# 06_LED_Config.net
KiCad netlist of a schematic drawn in Altium Designer
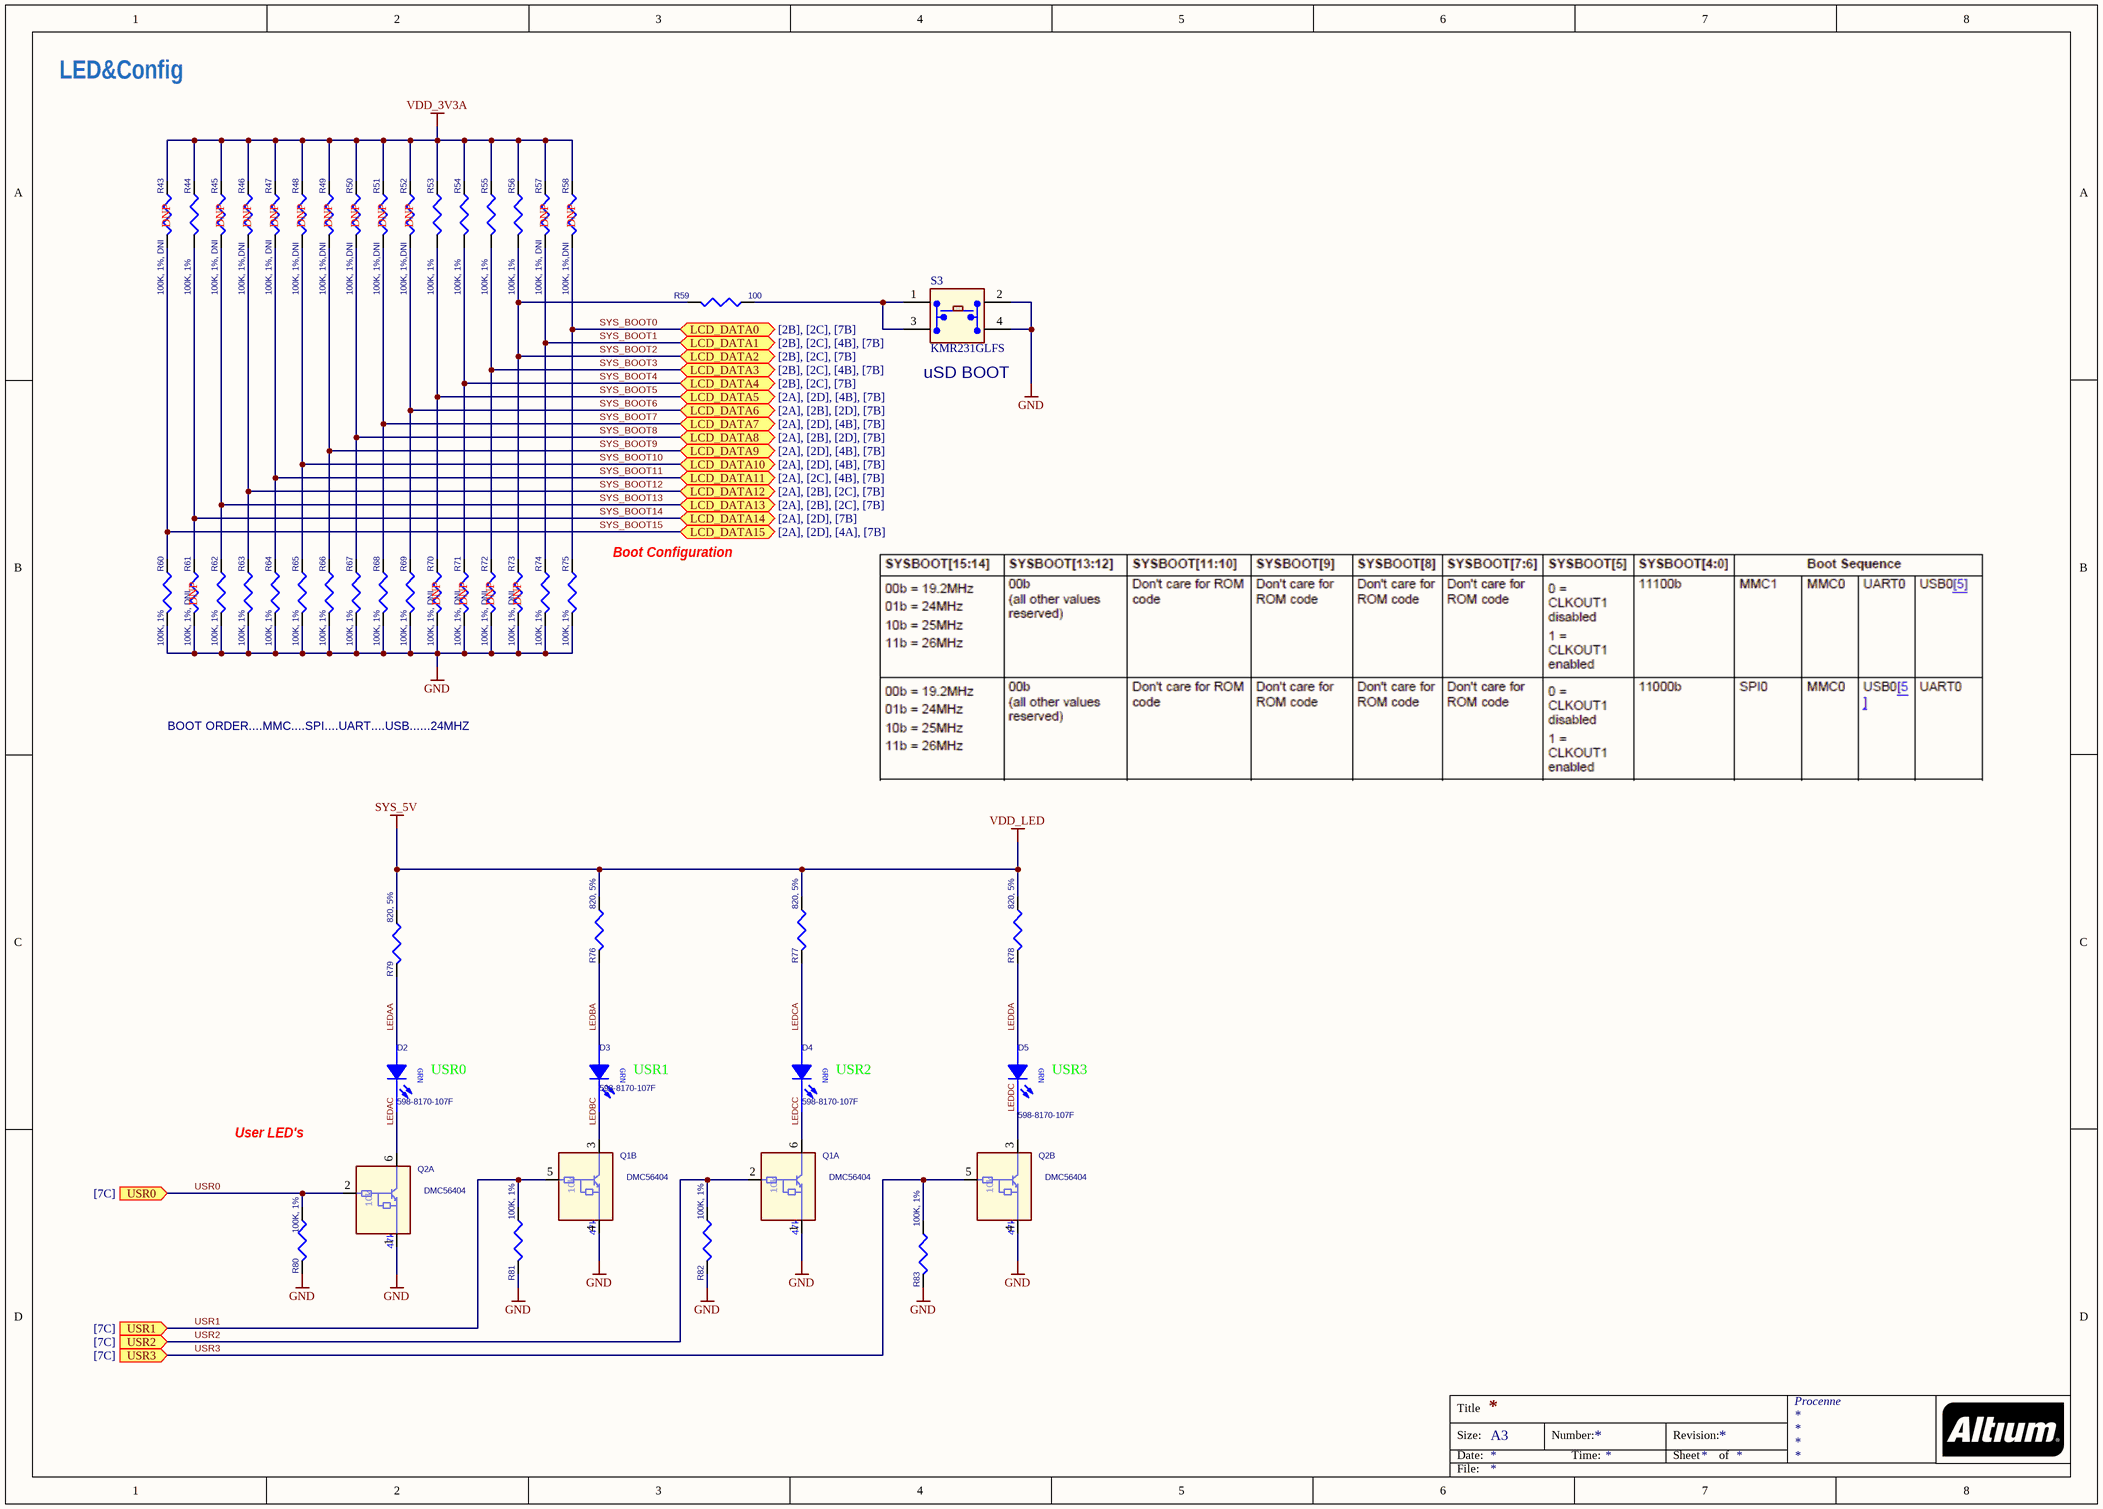
[diagram p0: 06_LED&Config.SchDoc]

(export (version "E")
  (design (tool "Eeschema 10.0.6"))
  (components
    (comp (ref "D2")
      (value "598-8170-107F")
      (footprint "LED_0603")
      (description "LED GREEN CLEAR 0805 SMD")
      (fields
        (field (name "MANUFACTURER") "Lite-On Inc")
        (field (name "MANUFACTURER PART NUMBER") "LTST-C170KGKT")
      )
      (libsource (lib "BEAGLEBONEBLACK_REV A5B") (part "LED_LTST-C150GKT"))
    )
    (comp (ref "D3")
      (value "598-8170-107F")
      (footprint "LED_0603")
      (description "LED GREEN CLEAR 0805 SMD")
      (fields
        (field (name "MANUFACTURER") "Lite-On Inc")
        (field (name "MANUFACTURER PART NUMBER") "LTST-C170KGKT")
      )
      (libsource (lib "BEAGLEBONEBLACK_REV A5B") (part "LED_LTST-C150GKT"))
    )
    (comp (ref "D4")
      (value "598-8170-107F")
      (footprint "LED_0603")
      (description "LED GREEN CLEAR 0805 SMD")
      (fields
        (field (name "MANUFACTURER") "Lite-On Inc")
        (field (name "MANUFACTURER PART NUMBER") "LTST-C170KGKT")
      )
      (libsource (lib "BEAGLEBONEBLACK_REV A5B") (part "LED_LTST-C150GKT"))
    )
    (comp (ref "D5")
      (value "598-8170-107F")
      (footprint "LED_0603")
      (description "LED GREEN CLEAR 0805 SMD")
      (fields
        (field (name "MANUFACTURER") "Lite-On Inc")
        (field (name "MANUFACTURER PART NUMBER") "LTST-C170KGKT")
      )
      (libsource (lib "BEAGLEBONEBLACK_REV A5B") (part "LED_LTST-C150GKT"))
    )
    (comp (ref "Q1")
      (value "DMC56404")
      (description "TRANS PREBIASED DUAL NPN SOT363")
      (fields
        (field (name "MANUFACTURER") "Toshiba")
        (field (name "MANUFACTURER PART NUMBER") "DDC114YU-7-F")
      )
      (libsource (lib "BEAGLEBONEBLACK_REV A5B") (part "RN1907"))
    )
    (comp (ref "Q2")
      (value "DMC56404")
      (description "TRANS PREBIASED DUAL NPN SOT363")
      (fields
        (field (name "MANUFACTURER") "Toshiba")
        (field (name "MANUFACTURER PART NUMBER") "DDC114YU-7-F")
      )
      (libsource (lib "BEAGLEBONEBLACK_REV A5B") (part "RN1907"))
    )
    (comp (ref "R43")
      (value "100K, 1%, DNI")
      (footprint "402")
      (description "RES 100K OHM 1/16W 1% 0402 SMD")
      (fields
        (field (name "MANUFACTURER") "Stackpole Electronics Inc")
        (field (name "MANUFACTURER PART NUMBER") "RMCF0402FT100K")
      )
      (libsource (lib "BEAGLEBONEBLACK_REV A5B") (part "RES_100K_1/16W_1%_0402"))
    )
    (comp (ref "R44")
      (value "100K, 1%")
      (footprint "402")
      (description "RES 100K OHM 1/16W 1% 0402 SMD")
      (fields
        (field (name "MANUFACTURER") "Stackpole Electronics Inc")
        (field (name "MANUFACTURER PART NUMBER") "RMCF0402FT100K")
      )
      (libsource (lib "BEAGLEBONEBLACK_REV A5B") (part "RES_100K_1/16W_1%_0402"))
    )
    (comp (ref "R45")
      (value "100K, 1%, DNI")
      (footprint "402")
      (description "RES 100K OHM 1/16W 1% 0402 SMD")
      (fields
        (field (name "MANUFACTURER") "Stackpole Electronics Inc")
        (field (name "MANUFACTURER PART NUMBER") "RMCF0402FT100K")
      )
      (libsource (lib "BEAGLEBONEBLACK_REV A5B") (part "RES_100K_1/16W_1%_0402"))
    )
    (comp (ref "R46")
      (value "100K, 1%,DNI")
      (footprint "402")
      (description "RES 100K OHM 1/16W 1% 0402 SMD")
      (fields
        (field (name "MANUFACTURER") "Stackpole Electronics Inc")
        (field (name "MANUFACTURER PART NUMBER") "RMCF0402FT100K")
      )
      (libsource (lib "BEAGLEBONEBLACK_REV A5B") (part "RES_100K_1/16W_1%_0402"))
    )
    (comp (ref "R47")
      (value "100K, 1%, DNI")
      (footprint "402")
      (description "RES 100K OHM 1/16W 1% 0402 SMD")
      (fields
        (field (name "MANUFACTURER") "Stackpole Electronics Inc")
        (field (name "MANUFACTURER PART NUMBER") "RMCF0402FT100K")
      )
      (libsource (lib "BEAGLEBONEBLACK_REV A5B") (part "RES_100K_1/16W_1%_0402"))
    )
    (comp (ref "R48")
      (value "100K, 1%,DNI")
      (footprint "402")
      (description "RES 100K OHM 1/16W 1% 0402 SMD")
      (fields
        (field (name "MANUFACTURER") "Stackpole Electronics Inc")
        (field (name "MANUFACTURER PART NUMBER") "RMCF0402FT100K")
      )
      (libsource (lib "BEAGLEBONEBLACK_REV A5B") (part "RES_100K_1/16W_1%_0402"))
    )
    (comp (ref "R49")
      (value "100K, 1%,DNI")
      (footprint "402")
      (description "RES 100K OHM 1/16W 1% 0402 SMD")
      (fields
        (field (name "MANUFACTURER") "Stackpole Electronics Inc")
        (field (name "MANUFACTURER PART NUMBER") "RMCF0402FT100K")
      )
      (libsource (lib "BEAGLEBONEBLACK_REV A5B") (part "RES_100K_1/16W_1%_0402"))
    )
    (comp (ref "R50")
      (value "100K, 1%,DNI")
      (footprint "402")
      (description "RES 100K OHM 1/16W 1% 0402 SMD")
      (fields
        (field (name "MANUFACTURER") "Stackpole Electronics Inc")
        (field (name "MANUFACTURER PART NUMBER") "RMCF0402FT100K")
      )
      (libsource (lib "BEAGLEBONEBLACK_REV A5B") (part "RES_100K_1/16W_1%_0402"))
    )
    (comp (ref "R51")
      (value "100K, 1%,DNI")
      (footprint "402")
      (description "RES 100K OHM 1/16W 1% 0402 SMD")
      (fields
        (field (name "MANUFACTURER") "Stackpole Electronics Inc")
        (field (name "MANUFACTURER PART NUMBER") "RMCF0402FT100K")
      )
      (libsource (lib "BEAGLEBONEBLACK_REV A5B") (part "RES_100K_1/16W_1%_0402"))
    )
    (comp (ref "R52")
      (value "100K, 1%,DNI")
      (footprint "402")
      (description "RES 100K OHM 1/16W 1% 0402 SMD")
      (fields
        (field (name "MANUFACTURER") "Stackpole Electronics Inc")
        (field (name "MANUFACTURER PART NUMBER") "RMCF0402FT100K")
      )
      (libsource (lib "BEAGLEBONEBLACK_REV A5B") (part "RES_100K_1/16W_1%_0402"))
    )
    (comp (ref "R53")
      (value "100K, 1%")
      (footprint "402")
      (description "RES 100K OHM 1/16W 1% 0402 SMD")
      (fields
        (field (name "MANUFACTURER") "Stackpole Electronics Inc")
        (field (name "MANUFACTURER PART NUMBER") "RMCF0402FT100K")
      )
      (libsource (lib "BEAGLEBONEBLACK_REV A5B") (part "RES_100K_1/16W_1%_0402"))
    )
    (comp (ref "R54")
      (value "100K, 1%")
      (footprint "402")
      (description "RES 100K OHM 1/16W 1% 0402 SMD")
      (fields
        (field (name "MANUFACTURER") "Stackpole Electronics Inc")
        (field (name "MANUFACTURER PART NUMBER") "RMCF0402FT100K")
      )
      (libsource (lib "BEAGLEBONEBLACK_REV A5B") (part "RES_100K_1/16W_1%_0402"))
    )
    (comp (ref "R55")
      (value "100K, 1%")
      (footprint "402")
      (description "RES 100K OHM 1/16W 1% 0402 SMD")
      (fields
        (field (name "MANUFACTURER") "Stackpole Electronics Inc")
        (field (name "MANUFACTURER PART NUMBER") "RMCF0402FT100K")
      )
      (libsource (lib "BEAGLEBONEBLACK_REV A5B") (part "RES_100K_1/16W_1%_0402"))
    )
    (comp (ref "R56")
      (value "100K, 1%")
      (footprint "402")
      (description "RES 100K OHM 1/16W 1% 0402 SMD")
      (fields
        (field (name "MANUFACTURER") "Stackpole Electronics Inc")
        (field (name "MANUFACTURER PART NUMBER") "RMCF0402FT100K")
      )
      (libsource (lib "BEAGLEBONEBLACK_REV A5B") (part "RES_100K_1/16W_1%_0402"))
    )
    (comp (ref "R57")
      (value "100K, 1%, DNI")
      (footprint "402")
      (description "RES 100K OHM 1/16W 1% 0402 SMD")
      (fields
        (field (name "MANUFACTURER") "Stackpole Electronics Inc")
        (field (name "MANUFACTURER PART NUMBER") "RMCF0402FT100K")
      )
      (libsource (lib "BEAGLEBONEBLACK_REV A5B") (part "RES_100K_1/16W_1%_0402"))
    )
    (comp (ref "R58")
      (value "100K, 1%,DNI")
      (footprint "402")
      (description "RES 100K OHM 1/16W 1% 0402 SMD")
      (fields
        (field (name "MANUFACTURER") "Stackpole Electronics Inc")
        (field (name "MANUFACTURER PART NUMBER") "RMCF0402FT100K")
      )
      (libsource (lib "BEAGLEBONEBLACK_REV A5B") (part "RES_100K_1/16W_1%_0402"))
    )
    (comp (ref "R59")
      (value "100")
      (footprint "402")
      (description "RES 100 OHM 1/10W 5% 0402 SMD")
      (fields
        (field (name "MANUFACTURER") "Panasonic Electronic Components")
        (field (name "MANUFACTURER PART NUMBER") "ERJ-2RKF1000X")
      )
      (libsource (lib "BEAGLEBONEBLACK_REV A5B") (part "RES SMD"))
    )
    (comp (ref "R60")
      (value "100K, 1%")
      (footprint "402")
      (description "RES 100K OHM 1/16W 1% 0402 SMD")
      (fields
        (field (name "MANUFACTURER") "Stackpole Electronics Inc")
        (field (name "MANUFACTURER PART NUMBER") "RMCF0402FT100K")
      )
      (libsource (lib "BEAGLEBONEBLACK_REV A5B") (part "RES_100K_1/16W_1%_0402"))
    )
    (comp (ref "R61")
      (value "100K, 1%, DNI")
      (footprint "402")
      (description "RES 100K OHM 1/16W 1% 0402 SMD")
      (fields
        (field (name "MANUFACTURER") "Stackpole Electronics Inc")
        (field (name "MANUFACTURER PART NUMBER") "RMCF0402FT100K")
      )
      (libsource (lib "BEAGLEBONEBLACK_REV A5B") (part "RES_100K_1/16W_1%_0402"))
    )
    (comp (ref "R62")
      (value "100K, 1%")
      (footprint "402")
      (description "RES 100K OHM 1/16W 1% 0402 SMD")
      (fields
        (field (name "MANUFACTURER") "Stackpole Electronics Inc")
        (field (name "MANUFACTURER PART NUMBER") "RMCF0402FT100K")
      )
      (libsource (lib "BEAGLEBONEBLACK_REV A5B") (part "RES_100K_1/16W_1%_0402"))
    )
    (comp (ref "R63")
      (value "100K, 1%")
      (footprint "402")
      (description "RES 100K OHM 1/16W 1% 0402 SMD")
      (fields
        (field (name "MANUFACTURER") "Stackpole Electronics Inc")
        (field (name "MANUFACTURER PART NUMBER") "RMCF0402FT100K")
      )
      (libsource (lib "BEAGLEBONEBLACK_REV A5B") (part "RES_100K_1/16W_1%_0402"))
    )
    (comp (ref "R64")
      (value "100K, 1%")
      (footprint "402")
      (description "RES 100K OHM 1/16W 1% 0402 SMD")
      (fields
        (field (name "MANUFACTURER") "Stackpole Electronics Inc")
        (field (name "MANUFACTURER PART NUMBER") "RMCF0402FT100K")
      )
      (libsource (lib "BEAGLEBONEBLACK_REV A5B") (part "RES_100K_1/16W_1%_0402"))
    )
    (comp (ref "R65")
      (value "100K, 1%")
      (footprint "402")
      (description "RES 100K OHM 1/16W 1% 0402 SMD")
      (fields
        (field (name "MANUFACTURER") "Stackpole Electronics Inc")
        (field (name "MANUFACTURER PART NUMBER") "RMCF0402FT100K")
      )
      (libsource (lib "BEAGLEBONEBLACK_REV A5B") (part "RES_100K_1/16W_1%_0402"))
    )
    (comp (ref "R66")
      (value "100K, 1%")
      (footprint "402")
      (description "RES 100K OHM 1/16W 1% 0402 SMD")
      (fields
        (field (name "MANUFACTURER") "Stackpole Electronics Inc")
        (field (name "MANUFACTURER PART NUMBER") "RMCF0402FT100K")
      )
      (libsource (lib "BEAGLEBONEBLACK_REV A5B") (part "RES_100K_1/16W_1%_0402"))
    )
    (comp (ref "R67")
      (value "100K, 1%")
      (footprint "402")
      (description "RES 100K OHM 1/16W 1% 0402 SMD")
      (fields
        (field (name "MANUFACTURER") "Stackpole Electronics Inc")
        (field (name "MANUFACTURER PART NUMBER") "RMCF0402FT100K")
      )
      (libsource (lib "BEAGLEBONEBLACK_REV A5B") (part "RES_100K_1/16W_1%_0402"))
    )
    (comp (ref "R68")
      (value "100K, 1%")
      (footprint "402")
      (description "RES 100K OHM 1/16W 1% 0402 SMD")
      (fields
        (field (name "MANUFACTURER") "Stackpole Electronics Inc")
        (field (name "MANUFACTURER PART NUMBER") "RMCF0402FT100K")
      )
      (libsource (lib "BEAGLEBONEBLACK_REV A5B") (part "RES_100K_1/16W_1%_0402"))
    )
    (comp (ref "R69")
      (value "100K, 1%")
      (footprint "402")
      (description "RES 100K OHM 1/16W 1% 0402 SMD")
      (fields
        (field (name "MANUFACTURER") "Stackpole Electronics Inc")
        (field (name "MANUFACTURER PART NUMBER") "RMCF0402FT100K")
      )
      (libsource (lib "BEAGLEBONEBLACK_REV A5B") (part "RES_100K_1/16W_1%_0402"))
    )
    (comp (ref "R70")
      (value "100K, 1%, DNI")
      (footprint "402")
      (description "RES 100K OHM 1/16W 1% 0402 SMD")
      (fields
        (field (name "MANUFACTURER") "Stackpole Electronics Inc")
        (field (name "MANUFACTURER PART NUMBER") "RMCF0402FT100K")
      )
      (libsource (lib "BEAGLEBONEBLACK_REV A5B") (part "RES_100K_1/16W_1%_0402"))
    )
    (comp (ref "R71")
      (value "100K, 1%, DNI")
      (footprint "402")
      (description "RES 100K OHM 1/16W 1% 0402 SMD")
      (fields
        (field (name "MANUFACTURER") "Stackpole Electronics Inc")
        (field (name "MANUFACTURER PART NUMBER") "RMCF0402FT100K")
      )
      (libsource (lib "BEAGLEBONEBLACK_REV A5B") (part "RES_100K_1/16W_1%_0402"))
    )
    (comp (ref "R72")
      (value "100K, 1%, DNI")
      (footprint "402")
      (description "RES 100K OHM 1/16W 1% 0402 SMD")
      (fields
        (field (name "MANUFACTURER") "Stackpole Electronics Inc")
        (field (name "MANUFACTURER PART NUMBER") "RMCF0402FT100K")
      )
      (libsource (lib "BEAGLEBONEBLACK_REV A5B") (part "RES_100K_1/16W_1%_0402"))
    )
    (comp (ref "R73")
      (value "100K, 1%, DNI")
      (footprint "402")
      (description "RES 100K OHM 1/16W 1% 0402 SMD")
      (fields
        (field (name "MANUFACTURER") "Stackpole Electronics Inc")
        (field (name "MANUFACTURER PART NUMBER") "RMCF0402FT100K")
      )
      (libsource (lib "BEAGLEBONEBLACK_REV A5B") (part "RES_100K_1/16W_1%_0402"))
    )
    (comp (ref "R74")
      (value "100K, 1%")
      (footprint "402")
      (description "RES 100K OHM 1/16W 1% 0402 SMD")
      (fields
        (field (name "MANUFACTURER") "Stackpole Electronics Inc")
        (field (name "MANUFACTURER PART NUMBER") "RMCF0402FT100K")
      )
      (libsource (lib "BEAGLEBONEBLACK_REV A5B") (part "RES_100K_1/16W_1%_0402"))
    )
    (comp (ref "R75")
      (value "100K, 1%")
      (footprint "402")
      (description "RES 100K OHM 1/16W 1% 0402 SMD")
      (fields
        (field (name "MANUFACTURER") "Stackpole Electronics Inc")
        (field (name "MANUFACTURER PART NUMBER") "RMCF0402FT100K")
      )
      (libsource (lib "BEAGLEBONEBLACK_REV A5B") (part "RES_100K_1/16W_1%_0402"))
    )
    (comp (ref "R76")
      (value "820, 5%")
      (footprint "402")
      (description "RES 820 OHM 1/10W 5% 0402 SMD")
      (fields
        (field (name "MANUFACTURER") "Yageo")
        (field (name "MANUFACTURER PART NUMBER") "RC0402JR-07820RL")
      )
      (libsource (lib "BEAGLEBONEBLACK_REV A5B") (part "RES_470_1/10W_5%_0402"))
    )
    (comp (ref "R77")
      (value "820, 5%")
      (footprint "402")
      (description "RES 820 OHM 1/10W 5% 0402 SMD")
      (fields
        (field (name "MANUFACTURER") "Yageo")
        (field (name "MANUFACTURER PART NUMBER") "RC0402JR-07820RL")
      )
      (libsource (lib "BEAGLEBONEBLACK_REV A5B") (part "RES_470_1/10W_5%_0402"))
    )
    (comp (ref "R78")
      (value "820, 5%")
      (footprint "402")
      (description "RES 820 OHM 1/10W 5% 0402 SMD")
      (fields
        (field (name "MANUFACTURER") "Yageo")
        (field (name "MANUFACTURER PART NUMBER") "RC0402JR-07820RL")
      )
      (libsource (lib "BEAGLEBONEBLACK_REV A5B") (part "RES_470_1/10W_5%_0402"))
    )
    (comp (ref "R79")
      (value "820, 5%")
      (footprint "402")
      (description "RES 820 OHM 1/10W 5% 0402 SMD")
      (fields
        (field (name "MANUFACTURER") "Yageo")
        (field (name "MANUFACTURER PART NUMBER") "RC0402JR-07820RL")
      )
      (libsource (lib "BEAGLEBONEBLACK_REV A5B") (part "RES_470_1/10W_5%_0402"))
    )
    (comp (ref "R80")
      (value "100K, 1%")
      (footprint "402")
      (description "RES 100K OHM 1/16W 1% 0402 SMD")
      (fields
        (field (name "MANUFACTURER") "Stackpole Electronics Inc")
        (field (name "MANUFACTURER PART NUMBER") "RMCF0402FT100K")
      )
      (libsource (lib "BEAGLEBONEBLACK_REV A5B") (part "RES_100K_1/16W_1%_0402"))
    )
    (comp (ref "R81")
      (value "100K, 1%")
      (footprint "402")
      (description "RES 100K OHM 1/16W 1% 0402 SMD")
      (fields
        (field (name "MANUFACTURER") "Stackpole Electronics Inc")
        (field (name "MANUFACTURER PART NUMBER") "RMCF0402FT100K")
      )
      (libsource (lib "BEAGLEBONEBLACK_REV A5B") (part "RES_100K_1/16W_1%_0402"))
    )
    (comp (ref "R82")
      (value "100K, 1%")
      (footprint "402")
      (description "RES 100K OHM 1/16W 1% 0402 SMD")
      (fields
        (field (name "MANUFACTURER") "Stackpole Electronics Inc")
        (field (name "MANUFACTURER PART NUMBER") "RMCF0402FT100K")
      )
      (libsource (lib "BEAGLEBONEBLACK_REV A5B") (part "RES_100K_1/16W_1%_0402"))
    )
    (comp (ref "R83")
      (value "100K, 1%")
      (footprint "402")
      (description "RES 100K OHM 1/16W 1% 0402 SMD")
      (fields
        (field (name "MANUFACTURER") "Stackpole Electronics Inc")
        (field (name "MANUFACTURER PART NUMBER") "RMCF0402FT100K")
      )
      (libsource (lib "BEAGLEBONEBLACK_REV A5B") (part "RES_100K_1/16W_1%_0402"))
    )
    (comp (ref "S3")
      (value "KMR231GLFS")
      (footprint "SW4SMD_63X161LS")
      (description "Microminiature Tact Switch for SMT")
      (fields (field (name "MANUFACTURER") "C&K Components"))
      (libsource (lib "BEAGLEBONEBLACK_REV A5B") (part "KMR2"))
    )
  )
  (nets
    (net (code "1") (name "/LEDAA") (class "Default")
      (node (ref "D2") (pin "2") (pinfunction "A_2") (pintype "passive"))
      (node (ref "R79") (pin "2") (pinfunction "2_2") (pintype "passive"))
    )
    (net (code "2") (name "/LEDAC") (class "Default")
      (node (ref "D2") (pin "1") (pinfunction "C_1") (pintype "passive"))
      (node (ref "Q2") (pin "6") (pinfunction "3_6") (pintype "passive"))
    )
    (net (code "3") (name "/LEDBA") (class "Default")
      (node (ref "D3") (pin "2") (pinfunction "A_2") (pintype "passive"))
      (node (ref "R76") (pin "2") (pinfunction "2_2") (pintype "passive"))
    )
    (net (code "4") (name "/LEDBC") (class "Default")
      (node (ref "D3") (pin "1") (pinfunction "C_1") (pintype "passive"))
      (node (ref "Q1") (pin "3") (pinfunction "3_3") (pintype "passive"))
    )
    (net (code "5") (name "/LEDCA") (class "Default")
      (node (ref "D4") (pin "2") (pinfunction "A_2") (pintype "passive"))
      (node (ref "R77") (pin "2") (pinfunction "2_2") (pintype "passive"))
    )
    (net (code "6") (name "/LEDCC") (class "Default")
      (node (ref "D4") (pin "1") (pinfunction "C_1") (pintype "passive"))
      (node (ref "Q1") (pin "6") (pinfunction "3_6") (pintype "passive"))
    )
    (net (code "7") (name "/LEDDA") (class "Default")
      (node (ref "D5") (pin "2") (pinfunction "A_2") (pintype "passive"))
      (node (ref "R78") (pin "2") (pinfunction "2_2") (pintype "passive"))
    )
    (net (code "8") (name "/LEDDC") (class "Default")
      (node (ref "D5") (pin "1") (pinfunction "C_1") (pintype "passive"))
      (node (ref "Q2") (pin "3") (pinfunction "3_3") (pintype "passive"))
    )
    (net (code "9") (name "/SYS_BOOT0") (class "Default")
      (node (ref "R58") (pin "2") (pinfunction "2_2") (pintype "passive"))
      (node (ref "R75") (pin "1") (pinfunction "1_1") (pintype "passive"))
    )
    (net (code "10") (name "/SYS_BOOT1") (class "Default")
      (node (ref "R57") (pin "2") (pinfunction "2_2") (pintype "passive"))
      (node (ref "R74") (pin "1") (pinfunction "1_1") (pintype "passive"))
    )
    (net (code "11") (name "/SYS_BOOT2") (class "Default")
      (node (ref "R56") (pin "2") (pinfunction "2_2") (pintype "passive"))
      (node (ref "R59") (pin "1") (pinfunction "P1_1") (pintype "passive"))
      (node (ref "R73") (pin "1") (pinfunction "1_1") (pintype "passive"))
    )
    (net (code "12") (name "/SYS_BOOT3") (class "Default")
      (node (ref "R55") (pin "2") (pinfunction "2_2") (pintype "passive"))
      (node (ref "R72") (pin "1") (pinfunction "1_1") (pintype "passive"))
    )
    (net (code "13") (name "/SYS_BOOT4") (class "Default")
      (node (ref "R54") (pin "2") (pinfunction "2_2") (pintype "passive"))
      (node (ref "R71") (pin "1") (pinfunction "1_1") (pintype "passive"))
    )
    (net (code "14") (name "/SYS_BOOT5") (class "Default")
      (node (ref "R53") (pin "2") (pinfunction "2_2") (pintype "passive"))
      (node (ref "R70") (pin "1") (pinfunction "1_1") (pintype "passive"))
    )
    (net (code "15") (name "/SYS_BOOT6") (class "Default")
      (node (ref "R52") (pin "2") (pinfunction "2_2") (pintype "passive"))
      (node (ref "R69") (pin "1") (pinfunction "1_1") (pintype "passive"))
    )
    (net (code "16") (name "/SYS_BOOT7") (class "Default")
      (node (ref "R51") (pin "2") (pinfunction "2_2") (pintype "passive"))
      (node (ref "R68") (pin "1") (pinfunction "1_1") (pintype "passive"))
    )
    (net (code "17") (name "/SYS_BOOT8") (class "Default")
      (node (ref "R50") (pin "2") (pinfunction "2_2") (pintype "passive"))
      (node (ref "R67") (pin "1") (pinfunction "1_1") (pintype "passive"))
    )
    (net (code "18") (name "/SYS_BOOT9") (class "Default")
      (node (ref "R49") (pin "2") (pinfunction "2_2") (pintype "passive"))
      (node (ref "R66") (pin "1") (pinfunction "1_1") (pintype "passive"))
    )
    (net (code "19") (name "/SYS_BOOT10") (class "Default")
      (node (ref "R48") (pin "2") (pinfunction "2_2") (pintype "passive"))
      (node (ref "R65") (pin "1") (pinfunction "1_1") (pintype "passive"))
    )
    (net (code "20") (name "/SYS_BOOT11") (class "Default")
      (node (ref "R47") (pin "2") (pinfunction "2_2") (pintype "passive"))
      (node (ref "R64") (pin "1") (pinfunction "1_1") (pintype "passive"))
    )
    (net (code "21") (name "/SYS_BOOT12") (class "Default")
      (node (ref "R46") (pin "2") (pinfunction "2_2") (pintype "passive"))
      (node (ref "R63") (pin "1") (pinfunction "1_1") (pintype "passive"))
    )
    (net (code "22") (name "/SYS_BOOT13") (class "Default")
      (node (ref "R45") (pin "2") (pinfunction "2_2") (pintype "passive"))
      (node (ref "R62") (pin "1") (pinfunction "1_1") (pintype "passive"))
    )
    (net (code "23") (name "/SYS_BOOT14") (class "Default")
      (node (ref "R44") (pin "2") (pinfunction "2_2") (pintype "passive"))
      (node (ref "R61") (pin "1") (pinfunction "1_1") (pintype "passive"))
    )
    (net (code "24") (name "/SYS_BOOT15") (class "Default")
      (node (ref "R43") (pin "2") (pinfunction "2_2") (pintype "passive"))
      (node (ref "R60") (pin "1") (pinfunction "1_1") (pintype "passive"))
    )
    (net (code "25") (name "/USR0") (class "Default")
      (node (ref "Q2") (pin "2") (pinfunction "5_2") (pintype "passive"))
      (node (ref "R80") (pin "1") (pinfunction "1_1") (pintype "passive"))
    )
    (net (code "26") (name "/USR1") (class "Default")
      (node (ref "Q1") (pin "5") (pinfunction "5_5") (pintype "passive"))
      (node (ref "R81") (pin "1") (pinfunction "1_1") (pintype "passive"))
    )
    (net (code "27") (name "/USR2") (class "Default")
      (node (ref "Q1") (pin "2") (pinfunction "5_2") (pintype "passive"))
      (node (ref "R82") (pin "1") (pinfunction "1_1") (pintype "passive"))
    )
    (net (code "28") (name "/USR3") (class "Default")
      (node (ref "Q2") (pin "5") (pinfunction "5_5") (pintype "passive"))
      (node (ref "R83") (pin "1") (pinfunction "1_1") (pintype "passive"))
    )
    (net (code "29") (name "GND") (class "Default")
      (node (ref "Q1") (pin "1") (pinfunction "4_1") (pintype "passive"))
      (node (ref "Q1") (pin "4") (pinfunction "4_4") (pintype "passive"))
      (node (ref "Q2") (pin "1") (pinfunction "4_1") (pintype "passive"))
      (node (ref "Q2") (pin "4") (pinfunction "4_4") (pintype "passive"))
      (node (ref "R60") (pin "2") (pinfunction "2_2") (pintype "passive"))
      (node (ref "R61") (pin "2") (pinfunction "2_2") (pintype "passive"))
      (node (ref "R62") (pin "2") (pinfunction "2_2") (pintype "passive"))
      (node (ref "R63") (pin "2") (pinfunction "2_2") (pintype "passive"))
      (node (ref "R64") (pin "2") (pinfunction "2_2") (pintype "passive"))
      (node (ref "R65") (pin "2") (pinfunction "2_2") (pintype "passive"))
      (node (ref "R66") (pin "2") (pinfunction "2_2") (pintype "passive"))
      (node (ref "R67") (pin "2") (pinfunction "2_2") (pintype "passive"))
      (node (ref "R68") (pin "2") (pinfunction "2_2") (pintype "passive"))
      (node (ref "R69") (pin "2") (pinfunction "2_2") (pintype "passive"))
      (node (ref "R70") (pin "2") (pinfunction "2_2") (pintype "passive"))
      (node (ref "R71") (pin "2") (pinfunction "2_2") (pintype "passive"))
      (node (ref "R72") (pin "2") (pinfunction "2_2") (pintype "passive"))
      (node (ref "R73") (pin "2") (pinfunction "2_2") (pintype "passive"))
      (node (ref "R74") (pin "2") (pinfunction "2_2") (pintype "passive"))
      (node (ref "R75") (pin "2") (pinfunction "2_2") (pintype "passive"))
      (node (ref "R80") (pin "2") (pinfunction "2_2") (pintype "passive"))
      (node (ref "R81") (pin "2") (pinfunction "2_2") (pintype "passive"))
      (node (ref "R82") (pin "2") (pinfunction "2_2") (pintype "passive"))
      (node (ref "R83") (pin "2") (pinfunction "2_2") (pintype "passive"))
      (node (ref "S3") (pin "2") (pinfunction "A2_2") (pintype "passive"))
      (node (ref "S3") (pin "4") (pinfunction "4_4") (pintype "power_in"))
    )
    (net (code "30") (name "Net-(R59-P2)") (class "Default")
      (node (ref "R59") (pin "2") (pinfunction "P2_2") (pintype "passive"))
      (node (ref "S3") (pin "1") (pinfunction "A1_1") (pintype "passive"))
      (node (ref "S3") (pin "3") (pinfunction "A3_3") (pintype "passive"))
    )
    (net (code "31") (name "SYS_5V") (class "Default")
      (node (ref "R76") (pin "1") (pinfunction "1_1") (pintype "passive"))
      (node (ref "R77") (pin "1") (pinfunction "1_1") (pintype "passive"))
      (node (ref "R78") (pin "1") (pinfunction "1_1") (pintype "passive"))
      (node (ref "R79") (pin "1") (pinfunction "1_1") (pintype "passive"))
    )
    (net (code "32") (name "VDD_3V3A") (class "Default")
      (node (ref "R43") (pin "1") (pinfunction "1_1") (pintype "passive"))
      (node (ref "R44") (pin "1") (pinfunction "1_1") (pintype "passive"))
      (node (ref "R45") (pin "1") (pinfunction "1_1") (pintype "passive"))
      (node (ref "R46") (pin "1") (pinfunction "1_1") (pintype "passive"))
      (node (ref "R47") (pin "1") (pinfunction "1_1") (pintype "passive"))
      (node (ref "R48") (pin "1") (pinfunction "1_1") (pintype "passive"))
      (node (ref "R49") (pin "1") (pinfunction "1_1") (pintype "passive"))
      (node (ref "R50") (pin "1") (pinfunction "1_1") (pintype "passive"))
      (node (ref "R51") (pin "1") (pinfunction "1_1") (pintype "passive"))
      (node (ref "R52") (pin "1") (pinfunction "1_1") (pintype "passive"))
      (node (ref "R53") (pin "1") (pinfunction "1_1") (pintype "passive"))
      (node (ref "R54") (pin "1") (pinfunction "1_1") (pintype "passive"))
      (node (ref "R55") (pin "1") (pinfunction "1_1") (pintype "passive"))
      (node (ref "R56") (pin "1") (pinfunction "1_1") (pintype "passive"))
      (node (ref "R57") (pin "1") (pinfunction "1_1") (pintype "passive"))
      (node (ref "R58") (pin "1") (pinfunction "1_1") (pintype "passive"))
    )
  )
)
